# BI6.net
KiCad netlist of a schematic drawn in Altium Designer
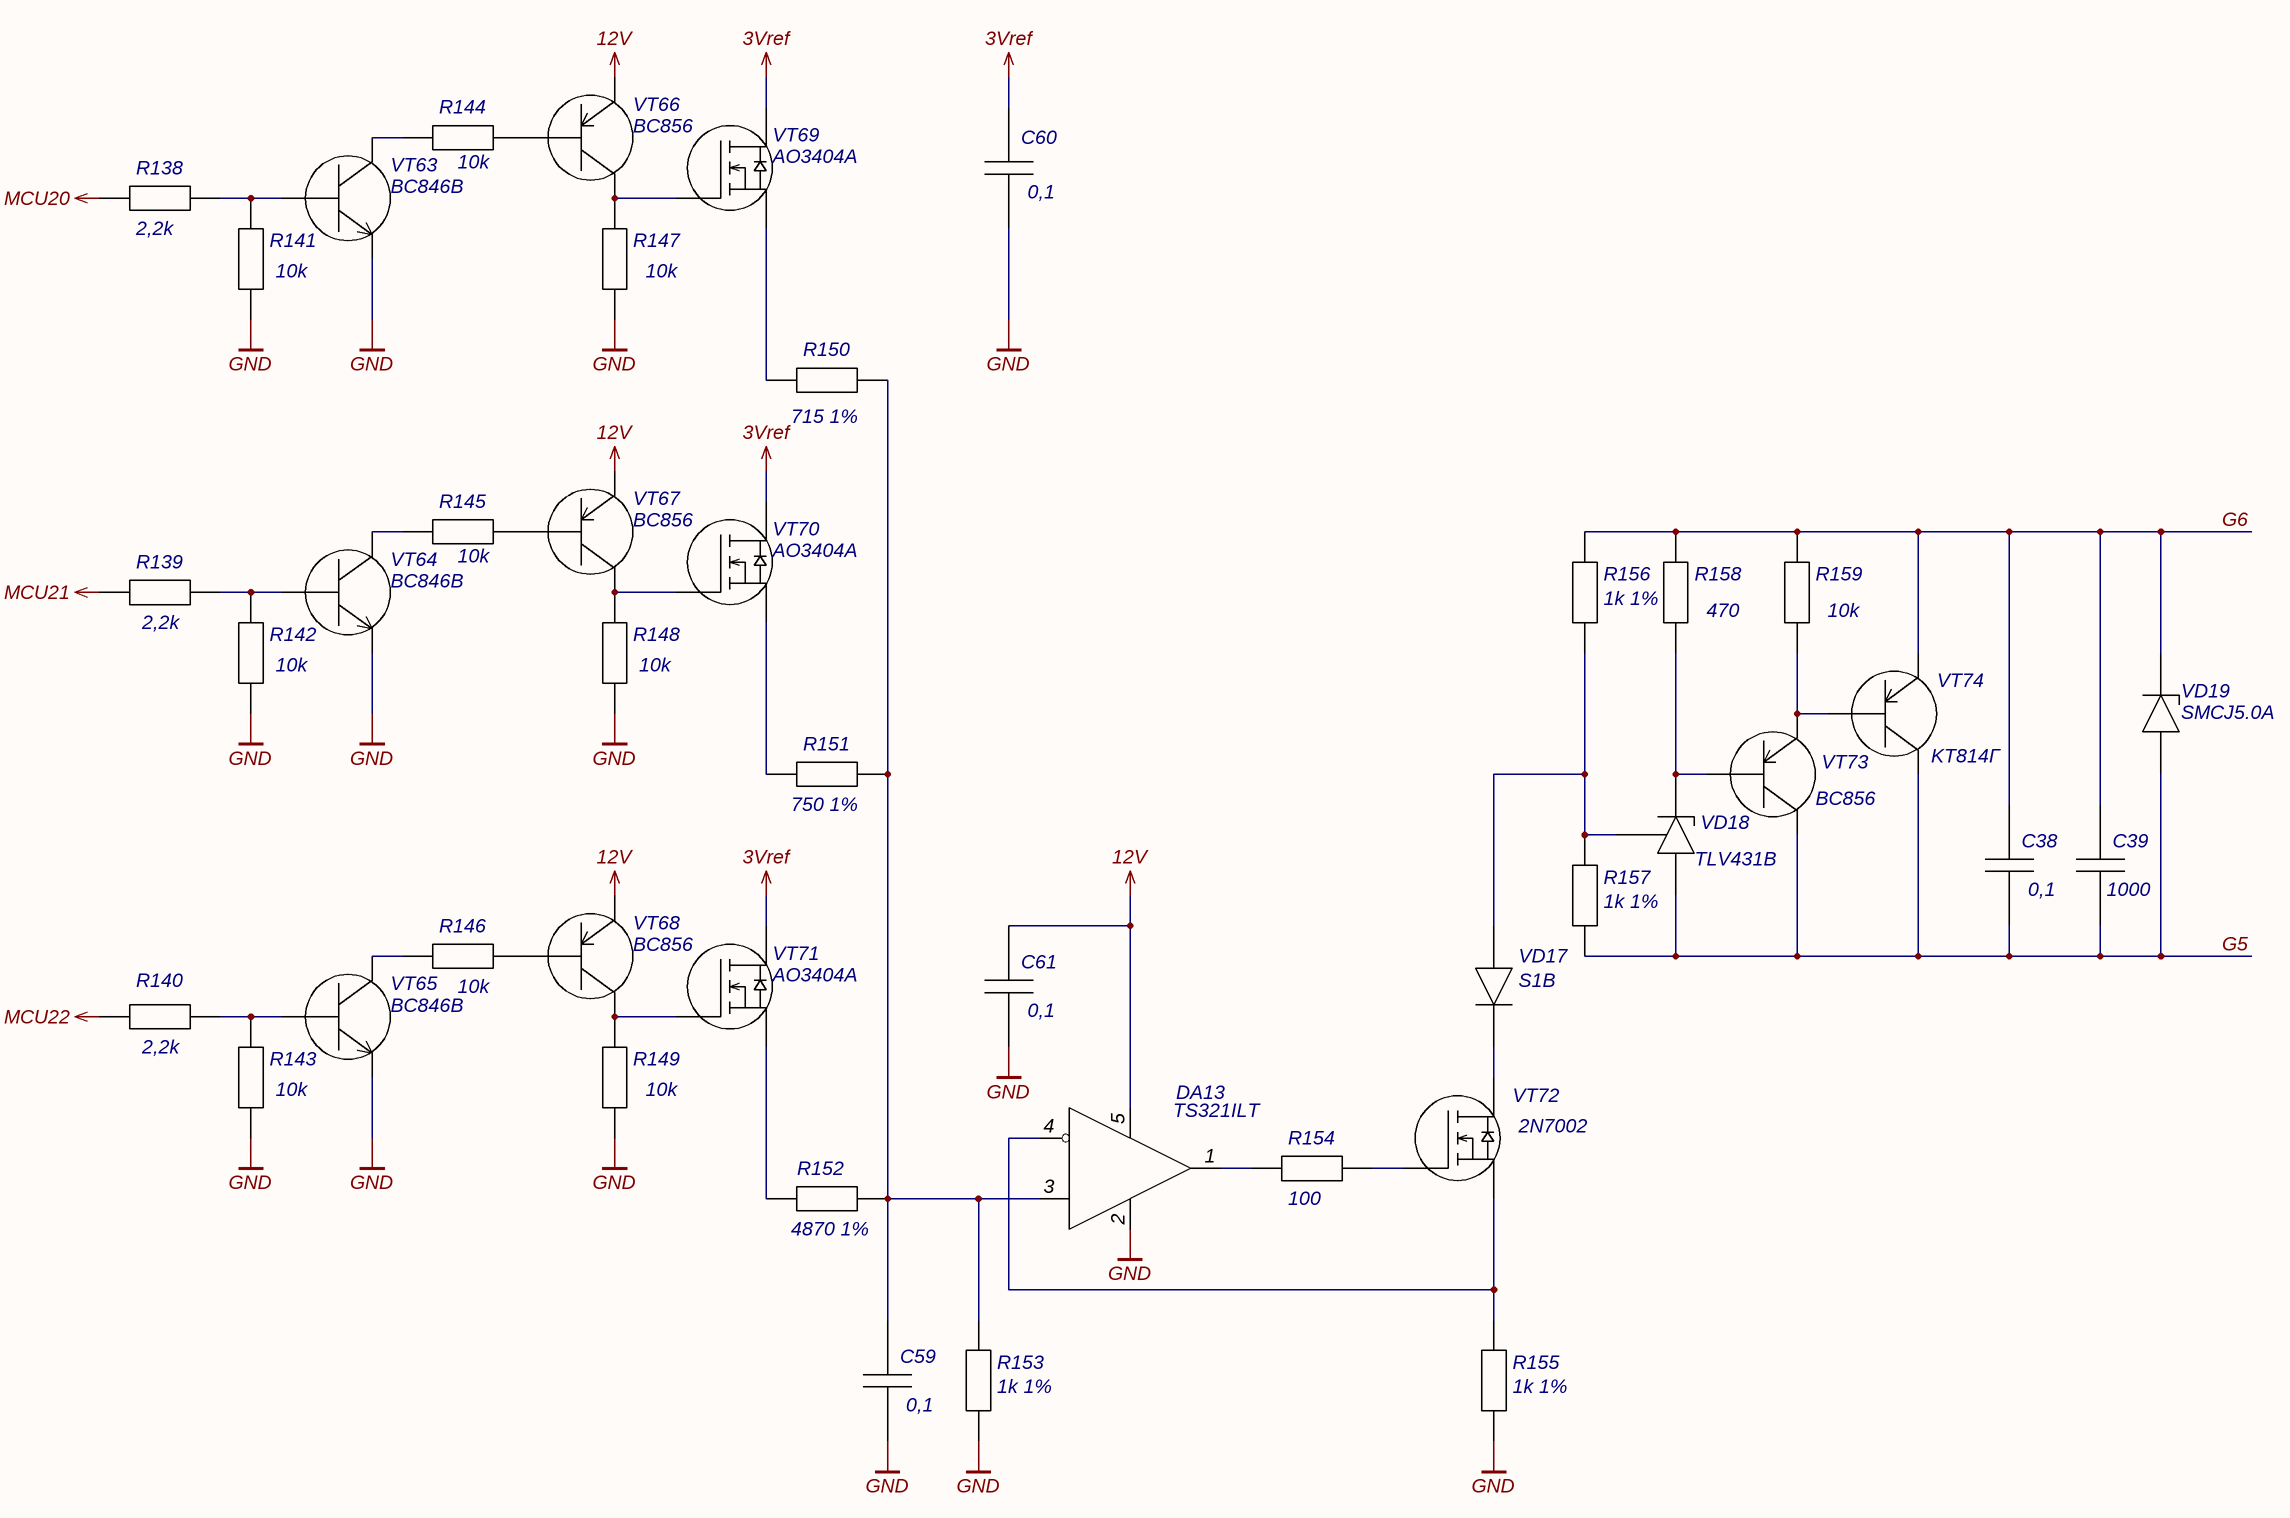
[diagram p0: BI6.SchDoc]

(export (version "E")
  (design (tool "Eeschema 10.0.6"))
  (components
    (comp (ref "C38")
      (value "0,1")
      (footprint "C0603")
      (description "Чип-конденсатор")
      (libsource (lib "Passive") (part "Chip Capasitor"))
    )
    (comp (ref "C39")
      (value "1000")
      (footprint "C0603")
      (description "Чип-конденсатор")
      (libsource (lib "Passive") (part "Chip Capasitor"))
    )
    (comp (ref "C59")
      (value "0,1")
      (footprint "C0603")
      (description "Чип-конденсатор")
      (libsource (lib "Passive") (part "Chip Capasitor"))
    )
    (comp (ref "C60")
      (value "0,1")
      (footprint "C0603")
      (description "Чип-конденсатор")
      (libsource (lib "Passive") (part "Chip Capasitor"))
    )
    (comp (ref "C61")
      (value "0,1")
      (footprint "C0603")
      (description "Чип-конденсатор")
      (libsource (lib "Passive") (part "Chip Capasitor"))
    )
    (comp (ref "DA13")
      (value "TS321ILT")
      (footprint "SOT-23-5")
      (description "1х Операционный усилитель")
      (libsource (lib "Schlib") (part "TS321ILT"))
    )
    (comp (ref "R138")
      (value "2,2k")
      (footprint "R0603")
      (description "Чип-резистор")
      (libsource (lib "Passive") (part "Chip Resistor"))
    )
    (comp (ref "R139")
      (value "2,2k")
      (footprint "R0603")
      (description "Чип-резистор")
      (libsource (lib "Passive") (part "Chip Resistor"))
    )
    (comp (ref "R140")
      (value "2,2k")
      (footprint "R0603")
      (description "Чип-резистор")
      (libsource (lib "Passive") (part "Chip Resistor"))
    )
    (comp (ref "R141")
      (value "10k")
      (footprint "R0603")
      (description "Чип-резистор")
      (libsource (lib "") (part "Chip Resistor_1"))
    )
    (comp (ref "R142")
      (value "10k")
      (footprint "R0603")
      (description "Чип-резистор")
      (libsource (lib "") (part "Chip Resistor_1"))
    )
    (comp (ref "R143")
      (value "10k")
      (footprint "R0603")
      (description "Чип-резистор")
      (libsource (lib "") (part "Chip Resistor_1"))
    )
    (comp (ref "R144")
      (value "10k")
      (footprint "R0603")
      (description "Чип-резистор")
      (libsource (lib "Passive") (part "Chip Resistor"))
    )
    (comp (ref "R145")
      (value "10k")
      (footprint "R0603")
      (description "Чип-резистор")
      (libsource (lib "Passive") (part "Chip Resistor"))
    )
    (comp (ref "R146")
      (value "10k")
      (footprint "R0603")
      (description "Чип-резистор")
      (libsource (lib "Passive") (part "Chip Resistor"))
    )
    (comp (ref "R147")
      (value "10k")
      (footprint "R0603")
      (description "Чип-резистор")
      (libsource (lib "") (part "Chip Resistor_1"))
    )
    (comp (ref "R148")
      (value "10k")
      (footprint "R0603")
      (description "Чип-резистор")
      (libsource (lib "") (part "Chip Resistor_1"))
    )
    (comp (ref "R149")
      (value "10k")
      (footprint "R0603")
      (description "Чип-резистор")
      (libsource (lib "") (part "Chip Resistor_1"))
    )
    (comp (ref "R150")
      (value "715 1%")
      (footprint "R0603")
      (description "Чип-резистор")
      (fields (field (name "PARTNUMBER") "RC0603FR-07715RL"))
      (libsource (lib "Passive") (part "Chip Resistor"))
    )
    (comp (ref "R151")
      (value "750 1%")
      (footprint "R0603")
      (description "Чип-резистор")
      (fields (field (name "PARTNUMBER") "RC0603FR-07750RL"))
      (libsource (lib "Passive") (part "Chip Resistor"))
    )
    (comp (ref "R152")
      (value "4870 1%")
      (footprint "R0603")
      (description "Чип-резистор")
      (fields (field (name "PARTNUMBER") "RC0603FR-074K87L"))
      (libsource (lib "Passive") (part "Chip Resistor"))
    )
    (comp (ref "R153")
      (value "1k 1%")
      (footprint "R0603")
      (description "Чип-резистор")
      (fields (field (name "PARTNUMBER") "CRCW06031K00FKEAC"))
      (libsource (lib "") (part "Chip Resistor_1"))
    )
    (comp (ref "R154")
      (value "100")
      (footprint "R0603")
      (description "Чип-резистор")
      (libsource (lib "Passive") (part "Chip Resistor"))
    )
    (comp (ref "R155")
      (value "1k 1%")
      (footprint "R0603")
      (description "Чип-резистор")
      (fields (field (name "PARTNUMBER") "CRCW06031K00FKEAC"))
      (libsource (lib "") (part "Chip Resistor_1"))
    )
    (comp (ref "R156")
      (value "1k 1%")
      (footprint "R0603")
      (description "Чип-резистор")
      (fields (field (name "PARTNUMBER") "CRCW06031K00FKEAC"))
      (libsource (lib "") (part "Chip Resistor_1"))
    )
    (comp (ref "R157")
      (value "1k 1%")
      (footprint "R0603")
      (description "Чип-резистор")
      (fields (field (name "PARTNUMBER") "CRCW06031K00FKEAC"))
      (libsource (lib "") (part "Chip Resistor_1"))
    )
    (comp (ref "R158")
      (value "470")
      (footprint "R0603")
      (description "Чип-резистор")
      (libsource (lib "") (part "Chip Resistor_1"))
    )
    (comp (ref "R159")
      (value "10k")
      (footprint "R0603")
      (description "Чип-резистор")
      (libsource (lib "") (part "Chip Resistor_1"))
    )
    (comp (ref "VD17")
      (value "S1B")
      (footprint "DO-214AC")
      (description "Диод выпрямительный, 100В")
      (fields (field (name "MANUFACTURER") "Diotec Semiconductor"))
      (libsource (lib "Schlib") (part "S1B"))
    )
    (comp (ref "VD18")
      (value "TLV431B")
      (footprint "SOT-23")
      (description "Стабилитрон регулируемый, 6В")
      (fields (field (name "MANUFACTURER") "Texas Instruments"))
      (libsource (lib "Schlib") (part "TLV431B"))
    )
    (comp (ref "VD19")
      (value "SMCJ5.0A")
      (footprint "DO-214AB")
      (description "Защитный диод, 5В")
      (fields (field (name "MANUFACTURER") "UTD Semiconductor Co.,Ltd"))
      (libsource (lib "Schlib") (part "SMCJ5.0A"))
    )
    (comp (ref "VT63")
      (value "BC846B")
      (footprint "SOT-23")
      (description "Транзистор биполярный NPN, 65В")
      (fields (field (name "MANUFACTURER") "Nexperia B.V."))
      (libsource (lib "Schlib") (part "BC846B"))
    )
    (comp (ref "VT64")
      (value "BC846B")
      (footprint "SOT-23")
      (description "Транзистор биполярный NPN, 65В")
      (fields (field (name "MANUFACTURER") "Nexperia B.V."))
      (libsource (lib "Schlib") (part "BC846B"))
    )
    (comp (ref "VT65")
      (value "BC846B")
      (footprint "SOT-23")
      (description "Транзистор биполярный NPN, 65В")
      (fields (field (name "MANUFACTURER") "Nexperia B.V."))
      (libsource (lib "Schlib") (part "BC846B"))
    )
    (comp (ref "VT66")
      (value "BC856")
      (footprint "SOT-23")
      (description "Транзистор биполярный PNP, 65В")
      (fields (field (name "MANUFACTURER") "Nexperia"))
      (libsource (lib "Schlib") (part "BC856"))
    )
    (comp (ref "VT67")
      (value "BC856")
      (footprint "SOT-23")
      (description "Транзистор биполярный PNP, 65В")
      (fields (field (name "MANUFACTURER") "Nexperia"))
      (libsource (lib "Schlib") (part "BC856"))
    )
    (comp (ref "VT68")
      (value "BC856")
      (footprint "SOT-23")
      (description "Транзистор биполярный PNP, 65В")
      (fields (field (name "MANUFACTURER") "Nexperia"))
      (libsource (lib "Schlib") (part "BC856"))
    )
    (comp (ref "VT69")
      (value "AO3404A")
      (footprint "SOT-23")
      (description "Транзистор MOSFET N-канал, 30В")
      (fields (field (name "MANUFACTURER") "UTD Semiconductor Co.,Ltd"))
      (libsource (lib "Schlib") (part "AO3404A"))
    )
    (comp (ref "VT70")
      (value "AO3404A")
      (footprint "SOT-23")
      (description "Транзистор MOSFET N-канал, 30В")
      (fields (field (name "MANUFACTURER") "UTD Semiconductor Co.,Ltd"))
      (libsource (lib "Schlib") (part "AO3404A"))
    )
    (comp (ref "VT71")
      (value "AO3404A")
      (footprint "SOT-23")
      (description "Транзистор MOSFET N-канал, 30В")
      (fields (field (name "MANUFACTURER") "UTD Semiconductor Co.,Ltd"))
      (libsource (lib "Schlib") (part "AO3404A"))
    )
    (comp (ref "VT72")
      (value "2N7002")
      (footprint "SOT-23")
      (description "Транзистор MOSFET N-канал, 60В")
      (fields (field (name "MANUFACTURER") "UTD Semiconductor Co."))
      (libsource (lib "Schlib") (part "2N7002"))
    )
    (comp (ref "VT73")
      (value "BC856")
      (footprint "SOT-23")
      (description "Транзистор биполярный PNP, 65В")
      (fields (field (name "MANUFACTURER") "Nexperia"))
      (libsource (lib "Schlib") (part "BC856"))
    )
    (comp (ref "VT74")
      (value "KT814Г")
      (footprint "TO-126")
      (description "Транзистор биполярный PNP, 100В")
      (fields (field (name "MANUFACTURER") "АО «ГРУППА КРЕМНИЙ ЭЛ»"))
      (libsource (lib "Schlib") (part "KT814Г"))
    )
  )
  (nets
    (net (code "1") (name "/G5") (class "Default")
      (node (ref "C38") (pin "1") (pinfunction "1_1") (pintype "passive"))
      (node (ref "C39") (pin "1") (pinfunction "1_1") (pintype "passive"))
      (node (ref "R157") (pin "1") (pinfunction "1_1") (pintype "passive"))
      (node (ref "VD18") (pin "1") (pinfunction "1_1") (pintype "passive"))
      (node (ref "VD19") (pin "1") (pinfunction "1_1") (pintype "passive"))
      (node (ref "VT73") (pin "2") (pinfunction "2_2") (pintype "passive"))
      (node (ref "VT74") (pin "2") (pinfunction "2_2") (pintype "passive"))
    )
    (net (code "2") (name "/G6") (class "Default")
      (node (ref "C38") (pin "2") (pinfunction "2_2") (pintype "passive"))
      (node (ref "C39") (pin "2") (pinfunction "2_2") (pintype "passive"))
      (node (ref "R156") (pin "2") (pinfunction "2_2") (pintype "passive"))
      (node (ref "R158") (pin "2") (pinfunction "2_2") (pintype "passive"))
      (node (ref "R159") (pin "2") (pinfunction "2_2") (pintype "passive"))
      (node (ref "VD19") (pin "2") (pinfunction "2_2") (pintype "passive"))
      (node (ref "VT74") (pin "1") (pinfunction "1_1") (pintype "passive"))
    )
    (net (code "3") (name "3Vref") (class "Default")
      (node (ref "C60") (pin "2") (pinfunction "2_2") (pintype "passive"))
      (node (ref "VT69") (pin "2") (pinfunction "D_2") (pintype "passive"))
      (node (ref "VT70") (pin "2") (pinfunction "D_2") (pintype "passive"))
      (node (ref "VT71") (pin "2") (pinfunction "D_2") (pintype "passive"))
    )
    (net (code "4") (name "12V") (class "Default")
      (node (ref "C61") (pin "2") (pinfunction "2_2") (pintype "passive"))
      (node (ref "DA13") (pin "5") (pinfunction "Vcc_5") (pintype "passive"))
      (node (ref "VT66") (pin "1") (pinfunction "1_1") (pintype "passive"))
      (node (ref "VT67") (pin "1") (pinfunction "1_1") (pintype "passive"))
      (node (ref "VT68") (pin "1") (pinfunction "1_1") (pintype "passive"))
    )
    (net (code "5") (name "GND") (class "Default")
      (node (ref "C59") (pin "1") (pinfunction "1_1") (pintype "passive"))
      (node (ref "C60") (pin "1") (pinfunction "1_1") (pintype "passive"))
      (node (ref "C61") (pin "1") (pinfunction "1_1") (pintype "passive"))
      (node (ref "DA13") (pin "2") (pinfunction "GND_2") (pintype "passive"))
      (node (ref "R141") (pin "1") (pinfunction "1_1") (pintype "passive"))
      (node (ref "R142") (pin "1") (pinfunction "1_1") (pintype "passive"))
      (node (ref "R143") (pin "1") (pinfunction "1_1") (pintype "passive"))
      (node (ref "R147") (pin "1") (pinfunction "1_1") (pintype "passive"))
      (node (ref "R148") (pin "1") (pinfunction "1_1") (pintype "passive"))
      (node (ref "R149") (pin "1") (pinfunction "1_1") (pintype "passive"))
      (node (ref "R153") (pin "1") (pinfunction "1_1") (pintype "passive"))
      (node (ref "R155") (pin "1") (pinfunction "1_1") (pintype "passive"))
      (node (ref "VT63") (pin "2") (pinfunction "E_2") (pintype "passive"))
      (node (ref "VT64") (pin "2") (pinfunction "E_2") (pintype "passive"))
      (node (ref "VT65") (pin "2") (pinfunction "E_2") (pintype "passive"))
    )
    (net (code "6") (name "MCU20") (class "Default")
      (node (ref "R138") (pin "1") (pinfunction "1_1") (pintype "passive"))
    )
    (net (code "7") (name "MCU21") (class "Default")
      (node (ref "R139") (pin "1") (pinfunction "1_1") (pintype "passive"))
    )
    (net (code "8") (name "MCU22") (class "Default")
      (node (ref "R140") (pin "1") (pinfunction "1_1") (pintype "passive"))
    )
    (net (code "9") (name "Net-(DA13-+)") (class "Default")
      (node (ref "C59") (pin "2") (pinfunction "2_2") (pintype "passive"))
      (node (ref "DA13") (pin "3") (pinfunction "+_3") (pintype "passive"))
      (node (ref "R150") (pin "2") (pinfunction "2_2") (pintype "passive"))
      (node (ref "R151") (pin "2") (pinfunction "2_2") (pintype "passive"))
      (node (ref "R152") (pin "2") (pinfunction "2_2") (pintype "passive"))
      (node (ref "R153") (pin "2") (pinfunction "2_2") (pintype "passive"))
    )
    (net (code "10") (name "Net-(DA13--)") (class "Default")
      (node (ref "DA13") (pin "4") (pinfunction "-_4") (pintype "passive"))
      (node (ref "R155") (pin "2") (pinfunction "2_2") (pintype "passive"))
      (node (ref "VT72") (pin "3") (pinfunction "S_3") (pintype "passive"))
    )
    (net (code "11") (name "Net-(DA13-OUT)") (class "Default")
      (node (ref "DA13") (pin "1") (pinfunction "OUT_1") (pintype "passive"))
      (node (ref "R154") (pin "1") (pinfunction "1_1") (pintype "passive"))
    )
    (net (code "12") (name "Net-(R144-Pad2)") (class "Default")
      (node (ref "R144") (pin "2") (pinfunction "2_2") (pintype "passive"))
      (node (ref "VT66") (pin "3") (pinfunction "3_3") (pintype "passive"))
    )
    (net (code "13") (name "Net-(R145-Pad2)") (class "Default")
      (node (ref "R145") (pin "2") (pinfunction "2_2") (pintype "passive"))
      (node (ref "VT67") (pin "3") (pinfunction "3_3") (pintype "passive"))
    )
    (net (code "14") (name "Net-(R146-Pad2)") (class "Default")
      (node (ref "R146") (pin "2") (pinfunction "2_2") (pintype "passive"))
      (node (ref "VT68") (pin "3") (pinfunction "3_3") (pintype "passive"))
    )
    (net (code "15") (name "Net-(R156-Pad1)") (class "Default")
      (node (ref "R156") (pin "1") (pinfunction "1_1") (pintype "passive"))
      (node (ref "R157") (pin "2") (pinfunction "2_2") (pintype "passive"))
      (node (ref "VD17") (pin "1") (pinfunction "1_1") (pintype "passive"))
      (node (ref "VD18") (pin "3") (pinfunction "3_3") (pintype "passive"))
    )
    (net (code "16") (name "Net-(R158-Pad1)") (class "Default")
      (node (ref "R158") (pin "1") (pinfunction "1_1") (pintype "passive"))
      (node (ref "VD18") (pin "2") (pinfunction "2_2") (pintype "passive"))
      (node (ref "VT73") (pin "3") (pinfunction "3_3") (pintype "passive"))
    )
    (net (code "17") (name "Net-(R159-Pad1)") (class "Default")
      (node (ref "R159") (pin "1") (pinfunction "1_1") (pintype "passive"))
      (node (ref "VT73") (pin "1") (pinfunction "1_1") (pintype "passive"))
      (node (ref "VT74") (pin "3") (pinfunction "3_3") (pintype "passive"))
    )
    (net (code "18") (name "Net-(VT63-B)") (class "Default")
      (node (ref "R138") (pin "2") (pinfunction "2_2") (pintype "passive"))
      (node (ref "R141") (pin "2") (pinfunction "2_2") (pintype "passive"))
      (node (ref "VT63") (pin "1") (pinfunction "B_1") (pintype "passive"))
    )
    (net (code "19") (name "Net-(VT63-C)") (class "Default")
      (node (ref "R144") (pin "1") (pinfunction "1_1") (pintype "passive"))
      (node (ref "VT63") (pin "3") (pinfunction "C_3") (pintype "passive"))
    )
    (net (code "20") (name "Net-(VT64-B)") (class "Default")
      (node (ref "R139") (pin "2") (pinfunction "2_2") (pintype "passive"))
      (node (ref "R142") (pin "2") (pinfunction "2_2") (pintype "passive"))
      (node (ref "VT64") (pin "1") (pinfunction "B_1") (pintype "passive"))
    )
    (net (code "21") (name "Net-(VT64-C)") (class "Default")
      (node (ref "R145") (pin "1") (pinfunction "1_1") (pintype "passive"))
      (node (ref "VT64") (pin "3") (pinfunction "C_3") (pintype "passive"))
    )
    (net (code "22") (name "Net-(VT65-B)") (class "Default")
      (node (ref "R140") (pin "2") (pinfunction "2_2") (pintype "passive"))
      (node (ref "R143") (pin "2") (pinfunction "2_2") (pintype "passive"))
      (node (ref "VT65") (pin "1") (pinfunction "B_1") (pintype "passive"))
    )
    (net (code "23") (name "Net-(VT65-C)") (class "Default")
      (node (ref "R146") (pin "1") (pinfunction "1_1") (pintype "passive"))
      (node (ref "VT65") (pin "3") (pinfunction "C_3") (pintype "passive"))
    )
    (net (code "24") (name "Net-(VT69-G)") (class "Default")
      (node (ref "R147") (pin "2") (pinfunction "2_2") (pintype "passive"))
      (node (ref "VT66") (pin "2") (pinfunction "2_2") (pintype "passive"))
      (node (ref "VT69") (pin "1") (pinfunction "G_1") (pintype "passive"))
    )
    (net (code "25") (name "Net-(VT69-S)") (class "Default")
      (node (ref "R150") (pin "1") (pinfunction "1_1") (pintype "passive"))
      (node (ref "VT69") (pin "3") (pinfunction "S_3") (pintype "passive"))
    )
    (net (code "26") (name "Net-(VT70-G)") (class "Default")
      (node (ref "R148") (pin "2") (pinfunction "2_2") (pintype "passive"))
      (node (ref "VT67") (pin "2") (pinfunction "2_2") (pintype "passive"))
      (node (ref "VT70") (pin "1") (pinfunction "G_1") (pintype "passive"))
    )
    (net (code "27") (name "Net-(VT70-S)") (class "Default")
      (node (ref "R151") (pin "1") (pinfunction "1_1") (pintype "passive"))
      (node (ref "VT70") (pin "3") (pinfunction "S_3") (pintype "passive"))
    )
    (net (code "28") (name "Net-(VT71-G)") (class "Default")
      (node (ref "R149") (pin "2") (pinfunction "2_2") (pintype "passive"))
      (node (ref "VT68") (pin "2") (pinfunction "2_2") (pintype "passive"))
      (node (ref "VT71") (pin "1") (pinfunction "G_1") (pintype "passive"))
    )
    (net (code "29") (name "Net-(VT71-S)") (class "Default")
      (node (ref "R152") (pin "1") (pinfunction "1_1") (pintype "passive"))
      (node (ref "VT71") (pin "3") (pinfunction "S_3") (pintype "passive"))
    )
    (net (code "30") (name "Net-(VT72-D)") (class "Default")
      (node (ref "VD17") (pin "2") (pinfunction "2_2") (pintype "passive"))
      (node (ref "VT72") (pin "2") (pinfunction "D_2") (pintype "passive"))
    )
    (net (code "31") (name "Net-(VT72-G)") (class "Default")
      (node (ref "R154") (pin "2") (pinfunction "2_2") (pintype "passive"))
      (node (ref "VT72") (pin "1") (pinfunction "G_1") (pintype "passive"))
    )
  )
)
